# CPU_-_Power.net
KiCad netlist of a schematic drawn in Altium Designer
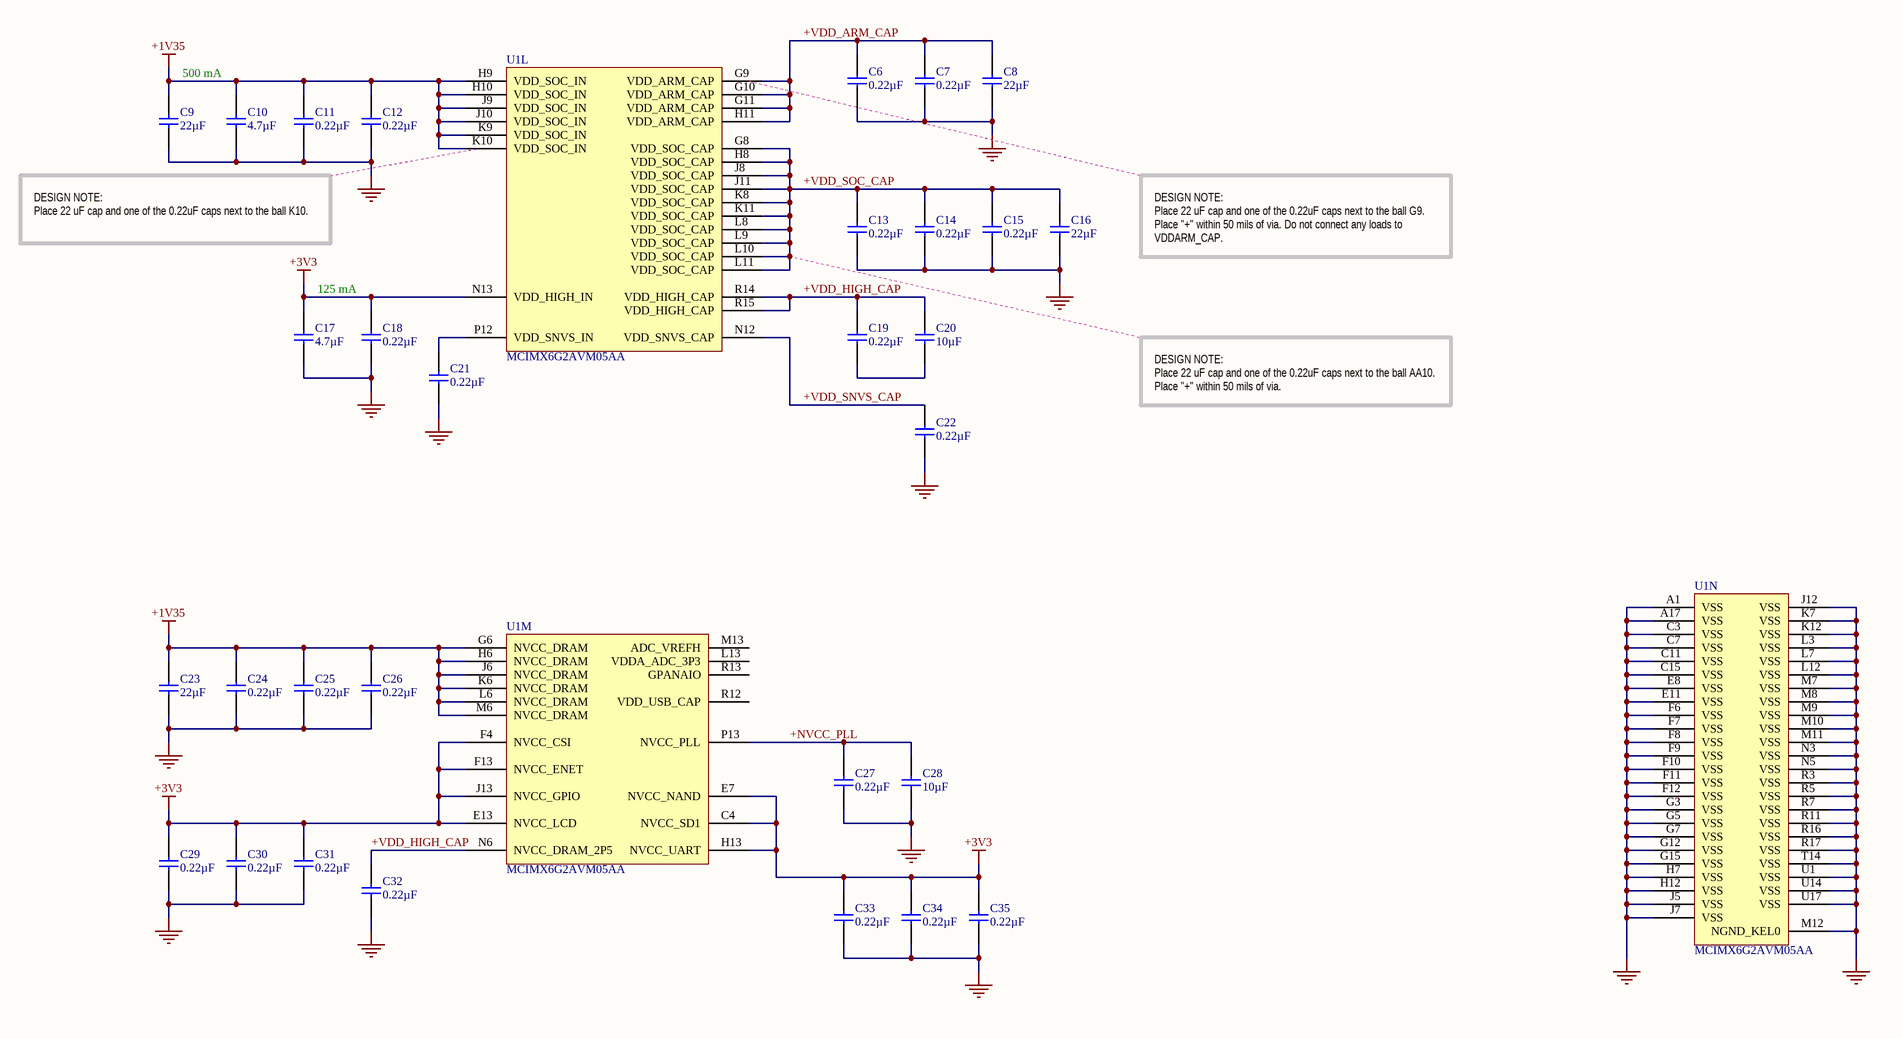
[diagram p0: CPU - Power.SchDoc]

(export (version "E")
  (design (tool "Eeschema 10.0.6"))
  (components
    (comp (ref "C6")
      (value "0.22µF")
      (footprint "CAP-0402-M")
      (fields
        (field (name "PART NUMBER") "CC0402KRX5R5BB224")
        (field (name "TOLERANCE") "±10%")
        (field (name "VOLTAGE") "6.3V")
      )
      (libsource (lib "Capacitors") (part "Capacitor"))
    )
    (comp (ref "C7")
      (value "0.22µF")
      (footprint "CAP-0402-M")
      (fields
        (field (name "PART NUMBER") "CC0402KRX5R5BB224")
        (field (name "TOLERANCE") "±10%")
        (field (name "VOLTAGE") "6.3V")
      )
      (libsource (lib "Capacitors") (part "Capacitor"))
    )
    (comp (ref "C8")
      (value "22µF")
      (footprint "CAP-0603-M")
      (fields
        (field (name "PART NUMBER") "CC0603MRX5R6BB226")
        (field (name "TOLERANCE") "±20%")
        (field (name "VOLTAGE") "10V")
      )
      (libsource (lib "Capacitors") (part "Capacitor"))
    )
    (comp (ref "C9")
      (value "22µF")
      (footprint "CAP-0603-M")
      (fields
        (field (name "PART NUMBER") "CC0603MRX5R6BB226")
        (field (name "TOLERANCE") "±20%")
        (field (name "VOLTAGE") "10V")
      )
      (libsource (lib "Capacitors") (part "Capacitor"))
    )
    (comp (ref "C10")
      (value "4.7µF")
      (footprint "CAP-0402-M")
      (fields
        (field (name "PART NUMBER") "CC0402MRX5R5BB475")
        (field (name "TOLERANCE") "±20%")
        (field (name "VOLTAGE") "6.3V")
      )
      (libsource (lib "Capacitors") (part "Capacitor"))
    )
    (comp (ref "C11")
      (value "0.22µF")
      (footprint "CAP-0402-M")
      (fields
        (field (name "PART NUMBER") "CC0402KRX5R5BB224")
        (field (name "TOLERANCE") "±10%")
        (field (name "VOLTAGE") "6.3V")
      )
      (libsource (lib "Capacitors") (part "Capacitor"))
    )
    (comp (ref "C12")
      (value "0.22µF")
      (footprint "CAP-0402-M")
      (fields
        (field (name "PART NUMBER") "CC0402KRX5R5BB224")
        (field (name "TOLERANCE") "±10%")
        (field (name "VOLTAGE") "6.3V")
      )
      (libsource (lib "Capacitors") (part "Capacitor"))
    )
    (comp (ref "C13")
      (value "0.22µF")
      (footprint "CAP-0402-M")
      (fields
        (field (name "PART NUMBER") "CC0402KRX5R5BB224")
        (field (name "TOLERANCE") "±10%")
        (field (name "VOLTAGE") "6.3V")
      )
      (libsource (lib "Capacitors") (part "Capacitor"))
    )
    (comp (ref "C14")
      (value "0.22µF")
      (footprint "CAP-0402-M")
      (fields
        (field (name "PART NUMBER") "CC0402KRX5R5BB224")
        (field (name "TOLERANCE") "±10%")
        (field (name "VOLTAGE") "6.3V")
      )
      (libsource (lib "Capacitors") (part "Capacitor"))
    )
    (comp (ref "C15")
      (value "0.22µF")
      (footprint "CAP-0402-M")
      (fields
        (field (name "PART NUMBER") "CC0402KRX5R5BB224")
        (field (name "TOLERANCE") "±10%")
        (field (name "VOLTAGE") "6.3V")
      )
      (libsource (lib "Capacitors") (part "Capacitor"))
    )
    (comp (ref "C16")
      (value "22µF")
      (footprint "CAP-0603-M")
      (fields
        (field (name "PART NUMBER") "CC0603MRX5R6BB226")
        (field (name "TOLERANCE") "±20%")
        (field (name "VOLTAGE") "10V")
      )
      (libsource (lib "Capacitors") (part "Capacitor"))
    )
    (comp (ref "C17")
      (value "4.7µF")
      (footprint "CAP-0402-M")
      (fields
        (field (name "PART NUMBER") "CC0402MRX5R5BB475")
        (field (name "TOLERANCE") "±20%")
        (field (name "VOLTAGE") "6.3V")
      )
      (libsource (lib "Capacitors") (part "Capacitor"))
    )
    (comp (ref "C18")
      (value "0.22µF")
      (footprint "CAP-0402-M")
      (fields
        (field (name "PART NUMBER") "CC0402KRX5R5BB224")
        (field (name "TOLERANCE") "±10%")
        (field (name "VOLTAGE") "6.3V")
      )
      (libsource (lib "Capacitors") (part "Capacitor"))
    )
    (comp (ref "C19")
      (value "0.22µF")
      (footprint "CAP-0402-M")
      (fields
        (field (name "PART NUMBER") "CC0402KRX5R5BB224")
        (field (name "TOLERANCE") "±10%")
        (field (name "VOLTAGE") "6.3V")
      )
      (libsource (lib "Capacitors") (part "Capacitor"))
    )
    (comp (ref "C20")
      (value "10µF")
      (footprint "CAP-0603-M")
      (fields
        (field (name "PART NUMBER") "CC0603MRX5R5BB106")
        (field (name "TOLERANCE") "±20%")
        (field (name "VOLTAGE") "6.3V")
      )
      (libsource (lib "Capacitors") (part "Capacitor"))
    )
    (comp (ref "C21")
      (value "0.22µF")
      (footprint "CAP-0402-M")
      (fields
        (field (name "PART NUMBER") "CC0402KRX5R5BB224")
        (field (name "TOLERANCE") "±10%")
        (field (name "VOLTAGE") "6.3V")
      )
      (libsource (lib "Capacitors") (part "Capacitor"))
    )
    (comp (ref "C22")
      (value "0.22µF")
      (footprint "CAP-0402-M")
      (fields
        (field (name "PART NUMBER") "CC0402KRX5R5BB224")
        (field (name "TOLERANCE") "±10%")
        (field (name "VOLTAGE") "6.3V")
      )
      (libsource (lib "Capacitors") (part "Capacitor"))
    )
    (comp (ref "C23")
      (value "22µF")
      (footprint "CAP-0603-M")
      (fields
        (field (name "PART NUMBER") "CC0603MRX5R6BB226")
        (field (name "TOLERANCE") "±20%")
        (field (name "VOLTAGE") "10V")
      )
      (libsource (lib "Capacitors") (part "Capacitor"))
    )
    (comp (ref "C24")
      (value "0.22µF")
      (footprint "CAP-0402-M")
      (fields
        (field (name "PART NUMBER") "CC0402KRX5R5BB224")
        (field (name "TOLERANCE") "±10%")
        (field (name "VOLTAGE") "6.3V")
      )
      (libsource (lib "Capacitors") (part "Capacitor"))
    )
    (comp (ref "C25")
      (value "0.22µF")
      (footprint "CAP-0402-M")
      (fields
        (field (name "PART NUMBER") "CC0402KRX5R5BB224")
        (field (name "TOLERANCE") "±10%")
        (field (name "VOLTAGE") "6.3V")
      )
      (libsource (lib "Capacitors") (part "Capacitor"))
    )
    (comp (ref "C26")
      (value "0.22µF")
      (footprint "CAP-0402-M")
      (fields
        (field (name "PART NUMBER") "CC0402KRX5R5BB224")
        (field (name "TOLERANCE") "±10%")
        (field (name "VOLTAGE") "6.3V")
      )
      (libsource (lib "Capacitors") (part "Capacitor"))
    )
    (comp (ref "C27")
      (value "0.22µF")
      (footprint "CAP-0402-M")
      (fields
        (field (name "PART NUMBER") "CC0402KRX5R5BB224")
        (field (name "TOLERANCE") "±10%")
        (field (name "VOLTAGE") "6.3V")
      )
      (libsource (lib "Capacitors") (part "Capacitor"))
    )
    (comp (ref "C28")
      (value "10µF")
      (footprint "CAP-0603-M")
      (fields
        (field (name "PART NUMBER") "CC0603MRX5R5BB106")
        (field (name "TOLERANCE") "±20%")
        (field (name "VOLTAGE") "6.3V")
      )
      (libsource (lib "Capacitors") (part "Capacitor"))
    )
    (comp (ref "C29")
      (value "0.22µF")
      (footprint "CAP-0402-M")
      (fields
        (field (name "PART NUMBER") "CC0402KRX5R5BB224")
        (field (name "TOLERANCE") "±10%")
        (field (name "VOLTAGE") "6.3V")
      )
      (libsource (lib "Capacitors") (part "Capacitor"))
    )
    (comp (ref "C30")
      (value "0.22µF")
      (footprint "CAP-0402-M")
      (fields
        (field (name "PART NUMBER") "CC0402KRX5R5BB224")
        (field (name "TOLERANCE") "±10%")
        (field (name "VOLTAGE") "6.3V")
      )
      (libsource (lib "Capacitors") (part "Capacitor"))
    )
    (comp (ref "C31")
      (value "0.22µF")
      (footprint "CAP-0402-M")
      (fields
        (field (name "PART NUMBER") "CC0402KRX5R5BB224")
        (field (name "TOLERANCE") "±10%")
        (field (name "VOLTAGE") "6.3V")
      )
      (libsource (lib "Capacitors") (part "Capacitor"))
    )
    (comp (ref "C32")
      (value "0.22µF")
      (footprint "CAP-0402-M")
      (fields
        (field (name "PART NUMBER") "CC0402KRX5R5BB224")
        (field (name "TOLERANCE") "±10%")
        (field (name "VOLTAGE") "6.3V")
      )
      (libsource (lib "Capacitors") (part "Capacitor"))
    )
    (comp (ref "C33")
      (value "0.22µF")
      (footprint "CAP-0402-M")
      (fields
        (field (name "PART NUMBER") "CC0402KRX5R5BB224")
        (field (name "TOLERANCE") "±10%")
        (field (name "VOLTAGE") "6.3V")
      )
      (libsource (lib "Capacitors") (part "Capacitor"))
    )
    (comp (ref "C34")
      (value "0.22µF")
      (footprint "CAP-0402-M")
      (fields
        (field (name "PART NUMBER") "CC0402KRX5R5BB224")
        (field (name "TOLERANCE") "±10%")
        (field (name "VOLTAGE") "6.3V")
      )
      (libsource (lib "Capacitors") (part "Capacitor"))
    )
    (comp (ref "C35")
      (value "0.22µF")
      (footprint "CAP-0402-M")
      (fields
        (field (name "PART NUMBER") "CC0402KRX5R5BB224")
        (field (name "TOLERANCE") "±10%")
        (field (name "VOLTAGE") "6.3V")
      )
      (libsource (lib "Capacitors") (part "Capacitor"))
    )
    (comp (ref "U1")
      (value "MCIMX6G2AVM05AA")
      (footprint "BGA289C80P17X17_1400X1400X132")
      (libsource (lib "Hub-UV17") (part "MCIMX6G2AVM05AA"))
    )
  )
  (nets
    (net (code "1") (name "+1V35") (class "Default")
      (node (ref "C10") (pin "2") (pinfunction "2_2") (pintype "passive"))
      (node (ref "C11") (pin "2") (pinfunction "2_2") (pintype "passive"))
      (node (ref "C12") (pin "2") (pinfunction "2_2") (pintype "passive"))
      (node (ref "C23") (pin "2") (pinfunction "2_2") (pintype "passive"))
      (node (ref "C24") (pin "2") (pinfunction "2_2") (pintype "passive"))
      (node (ref "C25") (pin "2") (pinfunction "2_2") (pintype "passive"))
      (node (ref "C26") (pin "2") (pinfunction "2_2") (pintype "passive"))
      (node (ref "C9") (pin "2") (pinfunction "2_2") (pintype "passive"))
      (node (ref "U1") (pin "G6") (pinfunction "NVCC_DRAM_G6") (pintype "power_in"))
      (node (ref "U1") (pin "H10") (pinfunction "VDD_SOC_IN_H10") (pintype "power_in"))
      (node (ref "U1") (pin "H6") (pinfunction "NVCC_DRAM_H6") (pintype "power_in"))
      (node (ref "U1") (pin "H9") (pinfunction "VDD_SOC_IN_H9") (pintype "power_in"))
      (node (ref "U1") (pin "J10") (pinfunction "VDD_SOC_IN_J10") (pintype "power_in"))
      (node (ref "U1") (pin "J6") (pinfunction "NVCC_DRAM_J6") (pintype "power_in"))
      (node (ref "U1") (pin "J9") (pinfunction "VDD_SOC_IN_J9") (pintype "power_in"))
      (node (ref "U1") (pin "K10") (pinfunction "VDD_SOC_IN_K10") (pintype "power_in"))
      (node (ref "U1") (pin "K6") (pinfunction "NVCC_DRAM_K6") (pintype "power_in"))
      (node (ref "U1") (pin "K9") (pinfunction "VDD_SOC_IN_K9") (pintype "power_in"))
      (node (ref "U1") (pin "L6") (pinfunction "NVCC_DRAM_L6") (pintype "power_in"))
      (node (ref "U1") (pin "M6") (pinfunction "NVCC_DRAM_M6") (pintype "power_in"))
    )
    (net (code "2") (name "+3V3") (class "Default")
      (node (ref "C17") (pin "2") (pinfunction "2_2") (pintype "passive"))
      (node (ref "C18") (pin "2") (pinfunction "2_2") (pintype "passive"))
      (node (ref "C29") (pin "2") (pinfunction "2_2") (pintype "passive"))
      (node (ref "C30") (pin "2") (pinfunction "2_2") (pintype "passive"))
      (node (ref "C31") (pin "2") (pinfunction "2_2") (pintype "passive"))
      (node (ref "C33") (pin "2") (pinfunction "2_2") (pintype "passive"))
      (node (ref "C34") (pin "2") (pinfunction "2_2") (pintype "passive"))
      (node (ref "C35") (pin "2") (pinfunction "2_2") (pintype "passive"))
      (node (ref "U1") (pin "C4") (pinfunction "NVCC_SD1_C4") (pintype "power_in"))
      (node (ref "U1") (pin "E13") (pinfunction "NVCC_LCD_E13") (pintype "power_in"))
      (node (ref "U1") (pin "E7") (pinfunction "NVCC_NAND_E7") (pintype "power_in"))
      (node (ref "U1") (pin "F13") (pinfunction "NVCC_ENET_F13") (pintype "power_in"))
      (node (ref "U1") (pin "F4") (pinfunction "NVCC_CSI_F4") (pintype "power_in"))
      (node (ref "U1") (pin "H13") (pinfunction "NVCC_UART_H13") (pintype "power_in"))
      (node (ref "U1") (pin "J13") (pinfunction "NVCC_GPIO_J13") (pintype "power_in"))
      (node (ref "U1") (pin "N13") (pinfunction "VDD_HIGH_IN_N13") (pintype "power_in"))
    )
    (net (code "3") (name "/+NVCC_PLL") (class "Default")
      (node (ref "C27") (pin "2") (pinfunction "2_2") (pintype "passive"))
      (node (ref "C28") (pin "2") (pinfunction "2_2") (pintype "passive"))
      (node (ref "U1") (pin "P13") (pinfunction "NVCC_PLL_P13") (pintype "power_in"))
    )
    (net (code "4") (name "/+VDD_ARM_CAP") (class "Default")
      (node (ref "C6") (pin "2") (pinfunction "2_2") (pintype "passive"))
      (node (ref "C7") (pin "2") (pinfunction "2_2") (pintype "passive"))
      (node (ref "C8") (pin "2") (pinfunction "2_2") (pintype "passive"))
      (node (ref "U1") (pin "G10") (pinfunction "VDD_ARM_CAP_G10") (pintype "power_in"))
      (node (ref "U1") (pin "G11") (pinfunction "VDD_ARM_CAP_G11") (pintype "power_in"))
      (node (ref "U1") (pin "G9") (pinfunction "VDD_ARM_CAP_G9") (pintype "power_in"))
      (node (ref "U1") (pin "H11") (pinfunction "VDD_ARM_CAP_H11") (pintype "power_in"))
    )
    (net (code "5") (name "/+VDD_HIGH_CAP") (class "Default")
      (node (ref "C19") (pin "2") (pinfunction "2_2") (pintype "passive"))
      (node (ref "C20") (pin "2") (pinfunction "2_2") (pintype "passive"))
      (node (ref "C32") (pin "2") (pinfunction "2_2") (pintype "passive"))
      (node (ref "U1") (pin "N6") (pinfunction "NVCC_DRAM_2P5_N6") (pintype "power_in"))
      (node (ref "U1") (pin "R14") (pinfunction "VDD_HIGH_CAP_R14") (pintype "power_in"))
      (node (ref "U1") (pin "R15") (pinfunction "VDD_HIGH_CAP_R15") (pintype "power_in"))
    )
    (net (code "6") (name "/+VDD_SNVS_CAP") (class "Default")
      (node (ref "C22") (pin "2") (pinfunction "2_2") (pintype "passive"))
      (node (ref "U1") (pin "N12") (pinfunction "VDD_SNVS_CAP_N12") (pintype "power_in"))
    )
    (net (code "7") (name "/+VDD_SOC_CAP") (class "Default")
      (node (ref "C13") (pin "2") (pinfunction "2_2") (pintype "passive"))
      (node (ref "C14") (pin "2") (pinfunction "2_2") (pintype "passive"))
      (node (ref "C15") (pin "2") (pinfunction "2_2") (pintype "passive"))
      (node (ref "C16") (pin "2") (pinfunction "2_2") (pintype "passive"))
      (node (ref "U1") (pin "G8") (pinfunction "VDD_SOC_CAP_G8") (pintype "power_in"))
      (node (ref "U1") (pin "H8") (pinfunction "VDD_SOC_CAP_H8") (pintype "power_in"))
      (node (ref "U1") (pin "J11") (pinfunction "VDD_SOC_CAP_J11") (pintype "power_in"))
      (node (ref "U1") (pin "J8") (pinfunction "VDD_SOC_CAP_J8") (pintype "power_in"))
      (node (ref "U1") (pin "K11") (pinfunction "VDD_SOC_CAP_K11") (pintype "power_in"))
      (node (ref "U1") (pin "K8") (pinfunction "VDD_SOC_CAP_K8") (pintype "power_in"))
      (node (ref "U1") (pin "L10") (pinfunction "VDD_SOC_CAP_L10") (pintype "power_in"))
      (node (ref "U1") (pin "L11") (pinfunction "VDD_SOC_CAP_L11") (pintype "power_in"))
      (node (ref "U1") (pin "L8") (pinfunction "VDD_SOC_CAP_L8") (pintype "power_in"))
      (node (ref "U1") (pin "L9") (pinfunction "VDD_SOC_CAP_L9") (pintype "power_in"))
    )
    (net (code "8") (name "GND") (class "Default")
      (node (ref "C10") (pin "1") (pinfunction "1_1") (pintype "passive"))
      (node (ref "C11") (pin "1") (pinfunction "1_1") (pintype "passive"))
      (node (ref "C12") (pin "1") (pinfunction "1_1") (pintype "passive"))
      (node (ref "C13") (pin "1") (pinfunction "1_1") (pintype "passive"))
      (node (ref "C14") (pin "1") (pinfunction "1_1") (pintype "passive"))
      (node (ref "C15") (pin "1") (pinfunction "1_1") (pintype "passive"))
      (node (ref "C16") (pin "1") (pinfunction "1_1") (pintype "passive"))
      (node (ref "C17") (pin "1") (pinfunction "1_1") (pintype "passive"))
      (node (ref "C18") (pin "1") (pinfunction "1_1") (pintype "passive"))
      (node (ref "C21") (pin "1") (pinfunction "1_1") (pintype "passive"))
      (node (ref "C22") (pin "1") (pinfunction "1_1") (pintype "passive"))
      (node (ref "C23") (pin "1") (pinfunction "1_1") (pintype "passive"))
      (node (ref "C24") (pin "1") (pinfunction "1_1") (pintype "passive"))
      (node (ref "C25") (pin "1") (pinfunction "1_1") (pintype "passive"))
      (node (ref "C26") (pin "1") (pinfunction "1_1") (pintype "passive"))
      (node (ref "C27") (pin "1") (pinfunction "1_1") (pintype "passive"))
      (node (ref "C28") (pin "1") (pinfunction "1_1") (pintype "passive"))
      (node (ref "C29") (pin "1") (pinfunction "1_1") (pintype "passive"))
      (node (ref "C30") (pin "1") (pinfunction "1_1") (pintype "passive"))
      (node (ref "C31") (pin "1") (pinfunction "1_1") (pintype "passive"))
      (node (ref "C32") (pin "1") (pinfunction "1_1") (pintype "passive"))
      (node (ref "C33") (pin "1") (pinfunction "1_1") (pintype "passive"))
      (node (ref "C34") (pin "1") (pinfunction "1_1") (pintype "passive"))
      (node (ref "C35") (pin "1") (pinfunction "1_1") (pintype "passive"))
      (node (ref "C6") (pin "1") (pinfunction "1_1") (pintype "passive"))
      (node (ref "C7") (pin "1") (pinfunction "1_1") (pintype "passive"))
      (node (ref "C8") (pin "1") (pinfunction "1_1") (pintype "passive"))
      (node (ref "C9") (pin "1") (pinfunction "1_1") (pintype "passive"))
      (node (ref "U1") (pin "A1") (pinfunction "VSS_A1") (pintype "passive"))
      (node (ref "U1") (pin "A17") (pinfunction "VSS_A17") (pintype "passive"))
      (node (ref "U1") (pin "C11") (pinfunction "VSS_C11") (pintype "passive"))
      (node (ref "U1") (pin "C15") (pinfunction "VSS_C15") (pintype "passive"))
      (node (ref "U1") (pin "C3") (pinfunction "VSS_C3") (pintype "passive"))
      (node (ref "U1") (pin "C7") (pinfunction "VSS_C7") (pintype "passive"))
      (node (ref "U1") (pin "E11") (pinfunction "VSS_E11") (pintype "passive"))
      (node (ref "U1") (pin "E8") (pinfunction "VSS_E8") (pintype "passive"))
      (node (ref "U1") (pin "F10") (pinfunction "VSS_F10") (pintype "passive"))
      (node (ref "U1") (pin "F11") (pinfunction "VSS_F11") (pintype "passive"))
      (node (ref "U1") (pin "F12") (pinfunction "VSS_F12") (pintype "passive"))
      (node (ref "U1") (pin "F6") (pinfunction "VSS_F6") (pintype "passive"))
      (node (ref "U1") (pin "F7") (pinfunction "VSS_F7") (pintype "passive"))
      (node (ref "U1") (pin "F8") (pinfunction "VSS_F8") (pintype "passive"))
      (node (ref "U1") (pin "F9") (pinfunction "VSS_F9") (pintype "passive"))
      (node (ref "U1") (pin "G12") (pinfunction "VSS_G12") (pintype "passive"))
      (node (ref "U1") (pin "G15") (pinfunction "VSS_G15") (pintype "passive"))
      (node (ref "U1") (pin "G3") (pinfunction "VSS_G3") (pintype "passive"))
      (node (ref "U1") (pin "G5") (pinfunction "VSS_G5") (pintype "passive"))
      (node (ref "U1") (pin "G7") (pinfunction "VSS_G7") (pintype "passive"))
      (node (ref "U1") (pin "H12") (pinfunction "VSS_H12") (pintype "passive"))
      (node (ref "U1") (pin "H7") (pinfunction "VSS_H7") (pintype "passive"))
      (node (ref "U1") (pin "J12") (pinfunction "VSS_J12") (pintype "passive"))
      (node (ref "U1") (pin "J5") (pinfunction "VSS_J5") (pintype "passive"))
      (node (ref "U1") (pin "J7") (pinfunction "VSS_J7") (pintype "passive"))
      (node (ref "U1") (pin "K12") (pinfunction "VSS_K12") (pintype "passive"))
      (node (ref "U1") (pin "K7") (pinfunction "VSS_K7") (pintype "passive"))
      (node (ref "U1") (pin "L12") (pinfunction "VSS_L12") (pintype "passive"))
      (node (ref "U1") (pin "L3") (pinfunction "VSS_L3") (pintype "passive"))
      (node (ref "U1") (pin "L7") (pinfunction "VSS_L7") (pintype "passive"))
      (node (ref "U1") (pin "M10") (pinfunction "VSS_M10") (pintype "passive"))
      (node (ref "U1") (pin "M11") (pinfunction "VSS_M11") (pintype "passive"))
      (node (ref "U1") (pin "M12") (pinfunction "NGND_KEL0_M12") (pintype "power_in"))
      (node (ref "U1") (pin "M7") (pinfunction "VSS_M7") (pintype "passive"))
      (node (ref "U1") (pin "M8") (pinfunction "VSS_M8") (pintype "passive"))
      (node (ref "U1") (pin "M9") (pinfunction "VSS_M9") (pintype "passive"))
      (node (ref "U1") (pin "N3") (pinfunction "VSS_N3") (pintype "passive"))
      (node (ref "U1") (pin "N5") (pinfunction "VSS_N5") (pintype "passive"))
      (node (ref "U1") (pin "R11") (pinfunction "VSS_R11") (pintype "passive"))
      (node (ref "U1") (pin "R16") (pinfunction "VSS_R16") (pintype "passive"))
      (node (ref "U1") (pin "R17") (pinfunction "VSS_R17") (pintype "passive"))
      (node (ref "U1") (pin "R3") (pinfunction "VSS_R3") (pintype "passive"))
      (node (ref "U1") (pin "R5") (pinfunction "VSS_R5") (pintype "passive"))
      (node (ref "U1") (pin "R7") (pinfunction "VSS_R7") (pintype "passive"))
      (node (ref "U1") (pin "T14") (pinfunction "VSS_T14") (pintype "passive"))
      (node (ref "U1") (pin "U1") (pinfunction "VSS_U1") (pintype "passive"))
      (node (ref "U1") (pin "U14") (pinfunction "VSS_U14") (pintype "passive"))
      (node (ref "U1") (pin "U17") (pinfunction "VSS_U17") (pintype "passive"))
    )
    (net (code "9") (name "Net-(C19-Pad1)") (class "Default")
      (node (ref "C19") (pin "1") (pinfunction "1_1") (pintype "passive"))
      (node (ref "C20") (pin "1") (pinfunction "1_1") (pintype "passive"))
    )
    (net (code "10") (name "Net-(U1L-VDD_SNVS_IN)") (class "Default")
      (node (ref "C21") (pin "2") (pinfunction "2_2") (pintype "passive"))
      (node (ref "U1") (pin "P12") (pinfunction "VDD_SNVS_IN_P12") (pintype "power_in"))
    )
    (net (code "11") (name "unconnected-(U1M-ADC_VREFH-PadM13)") (class "Default")
      (node (ref "U1") (pin "M13") (pinfunction "ADC_VREFH_M13") (pintype "power_in"))
    )
    (net (code "12") (name "unconnected-(U1M-GPANAIO-PadR13)") (class "Default")
      (node (ref "U1") (pin "R13") (pinfunction "GPANAIO_R13") (pintype "power_in"))
    )
    (net (code "13") (name "unconnected-(U1M-VDDA_ADC_3P3-PadL13)") (class "Default")
      (node (ref "U1") (pin "L13") (pinfunction "VDDA_ADC_3P3_L13") (pintype "power_in"))
    )
    (net (code "14") (name "unconnected-(U1M-VDD_USB_CAP-PadR12)") (class "Default")
      (node (ref "U1") (pin "R12") (pinfunction "VDD_USB_CAP_R12") (pintype "power_in"))
    )
  )
)
